# Halbbruecke.net
KiCad netlist of a schematic drawn in Altium Designer
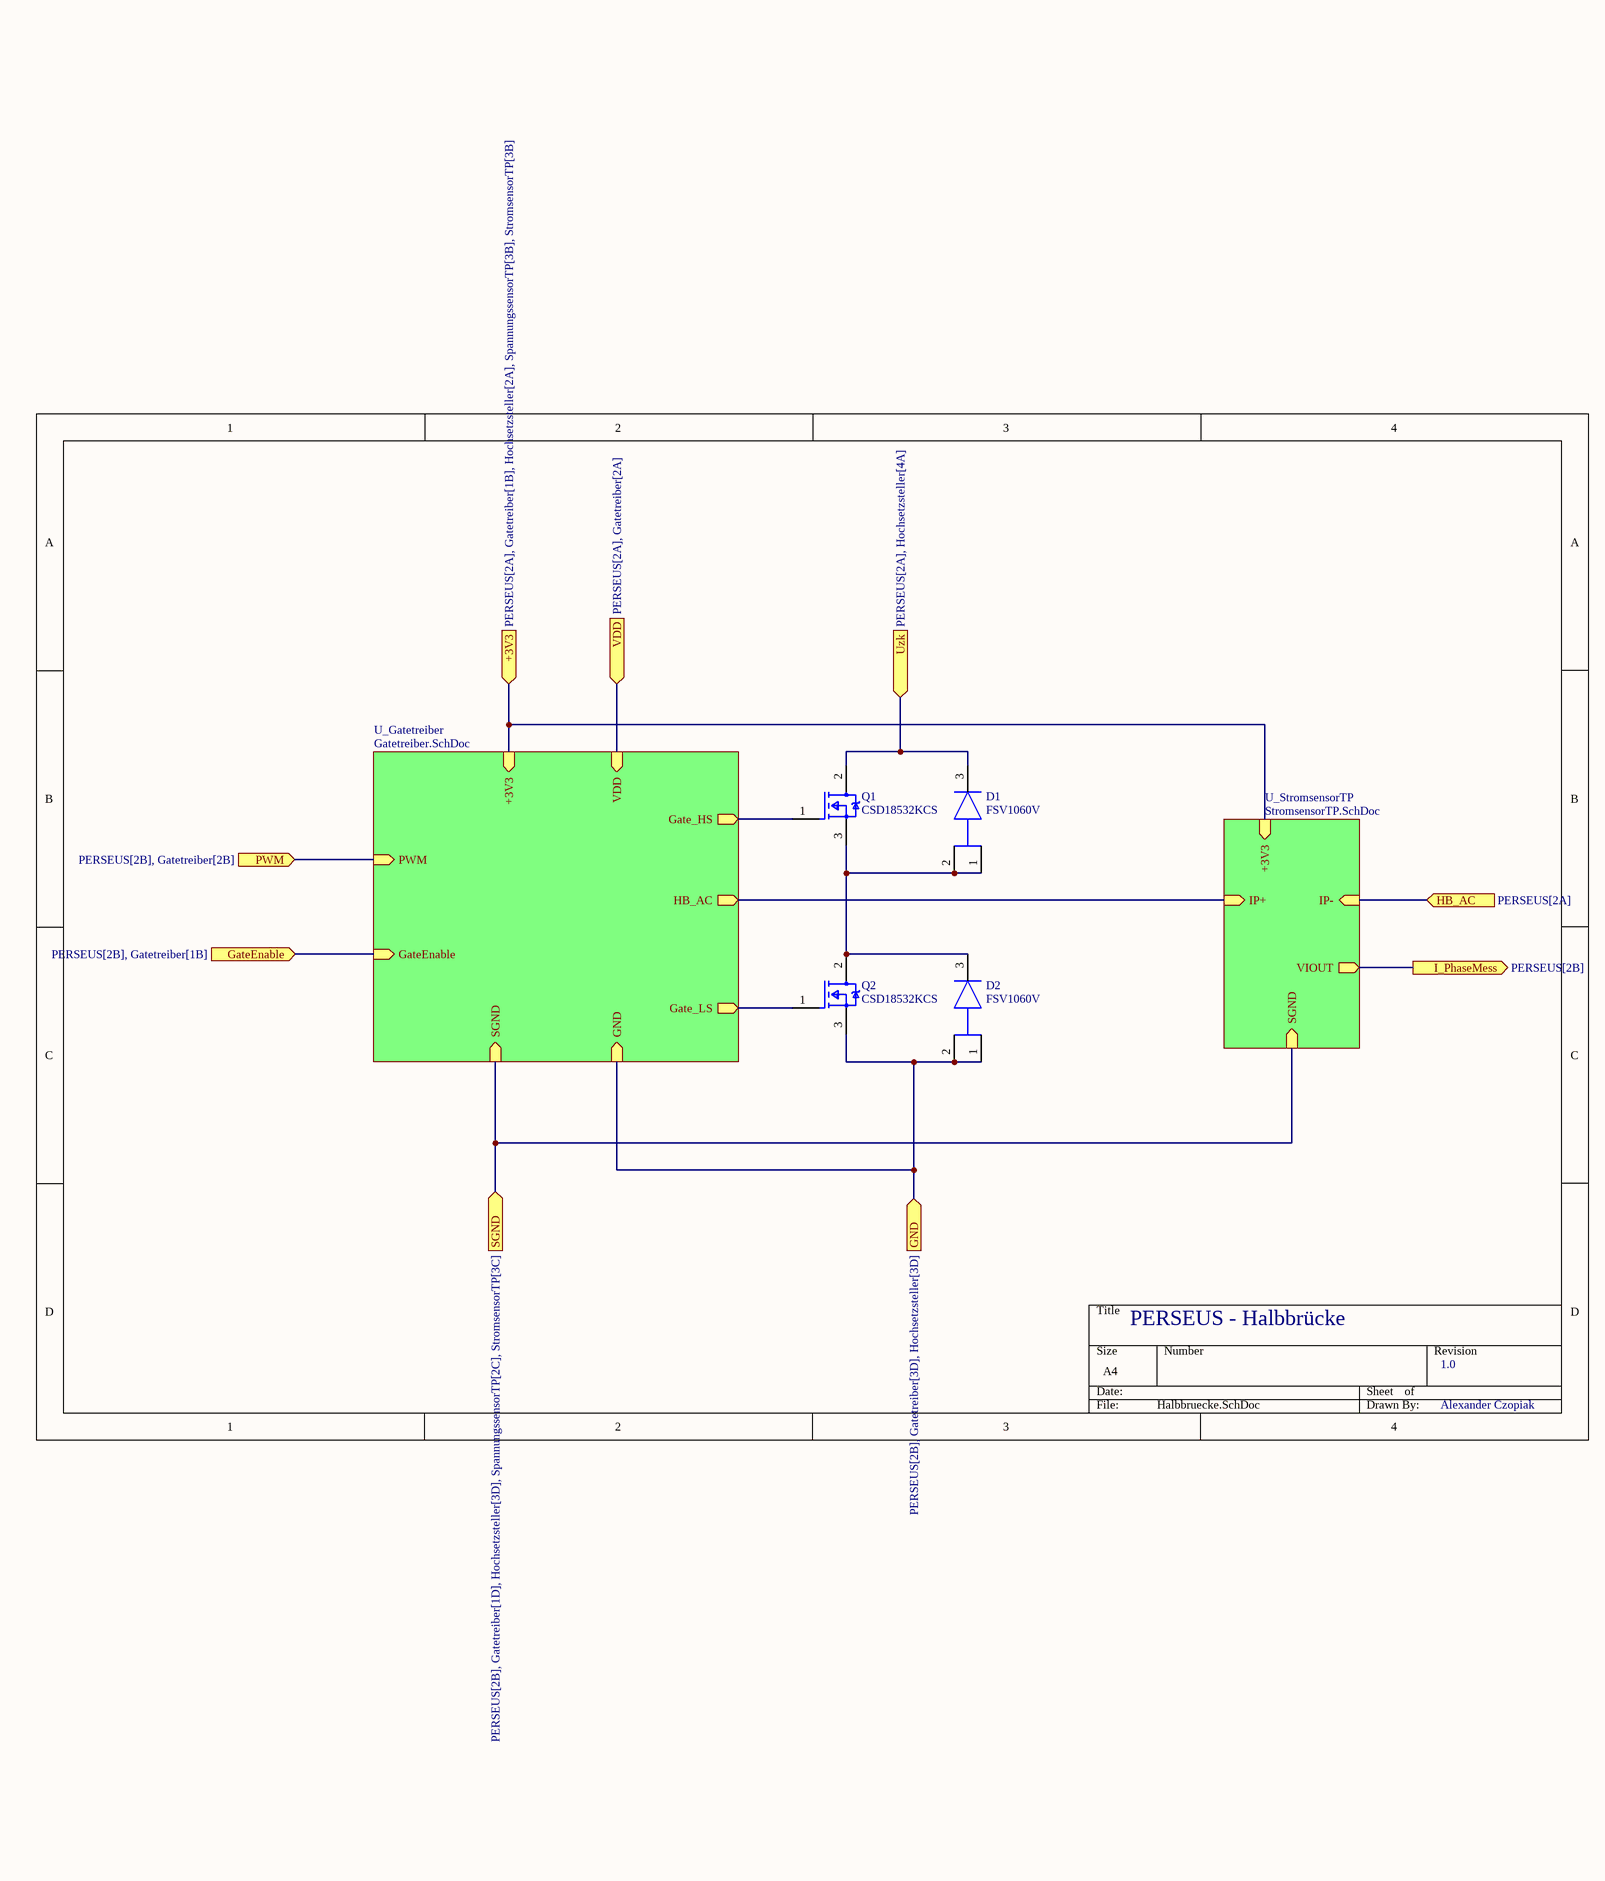
[diagram p0: Halbbruecke.SchDoc]

(export (version "E")
  (design (tool "Eeschema 10.0.6"))
  (components
    (comp (ref "D1")
      (value "FSV1060V")
      (footprint "FP-340BQ-MFG")
      (description "DIODE SCHOTTKY 60V 10A TO277-3")
      (fields
        (field (name "MANUFACTURER") "ON Semiconductor")
        (field (name "OCTOPART") "https://octopart.com/fsv1060v-on+semiconductor-84328651")
      )
      (libsource (lib "Altium Content Vault") (part "4936ed7bdd82a3c6bbc3cb868a43564"))
    )
    (comp (ref "D2")
      (value "FSV1060V")
      (footprint "FP-340BQ-MFG")
      (description "DIODE SCHOTTKY 60V 10A TO277-3")
      (fields
        (field (name "MANUFACTURER") "ON Semiconductor")
        (field (name "OCTOPART") "https://octopart.com/fsv1060v-on+semiconductor-84328651")
      )
      (libsource (lib "Altium Content Vault") (part "4936ed7bdd82a3c6bbc3cb868a43564"))
    )
    (comp (ref "Q1")
      (value "CSD18532KCS")
      (footprint "FP-PG-TO220-3-MFG")
      (description "MOSFET N-CH 60V 100A TO220")
      (libsource (lib "Altium Content Vault") (part "8b62d417cbef8344eebe0bde0c45977"))
    )
    (comp (ref "Q2")
      (value "CSD18532KCS")
      (footprint "FP-PG-TO220-3-MFG")
      (description "MOSFET N-CH 60V 100A TO220")
      (libsource (lib "Altium Content Vault") (part "8b62d417cbef8344eebe0bde0c45977"))
    )
  )
  (nets
    (net (code "2") (name "/GND") (class "Default")
      (node (ref "D2") (pin "1") (pinfunction "Anode_1_1") (pintype "passive"))
      (node (ref "D2") (pin "2") (pinfunction "Anode_2_2") (pintype "passive"))
      (node (ref "Q2") (pin "3") (pinfunction "SOURCE_3") (pintype "passive"))
    )
    (net (code "4") (name "/Gate_HS") (class "Default")
      (node (ref "Q1") (pin "1") (pinfunction "GATE_1") (pintype "passive"))
    )
    (net (code "5") (name "/Gate_LS") (class "Default")
      (node (ref "Q2") (pin "1") (pinfunction "GATE_1") (pintype "passive"))
    )
    (net (code "11") (name "/Uzk") (class "Default")
      (node (ref "D1") (pin "3") (pinfunction "C_3") (pintype "passive"))
      (node (ref "Q1") (pin "2") (pinfunction "DRAIN_2") (pintype "passive"))
    )
    (net (code "13") (name "Net-(D1-Anode_1)") (class "Default")
      (node (ref "D1") (pin "1") (pinfunction "Anode_1_1") (pintype "passive"))
      (node (ref "D1") (pin "2") (pinfunction "Anode_2_2") (pintype "passive"))
      (node (ref "D2") (pin "3") (pinfunction "C_3") (pintype "passive"))
      (node (ref "Q1") (pin "3") (pinfunction "SOURCE_3") (pintype "passive"))
      (node (ref "Q2") (pin "2") (pinfunction "DRAIN_2") (pintype "passive"))
    )
  )
)
